# SchemeP1.net
KiCad netlist of a schematic drawn in Altium Designer
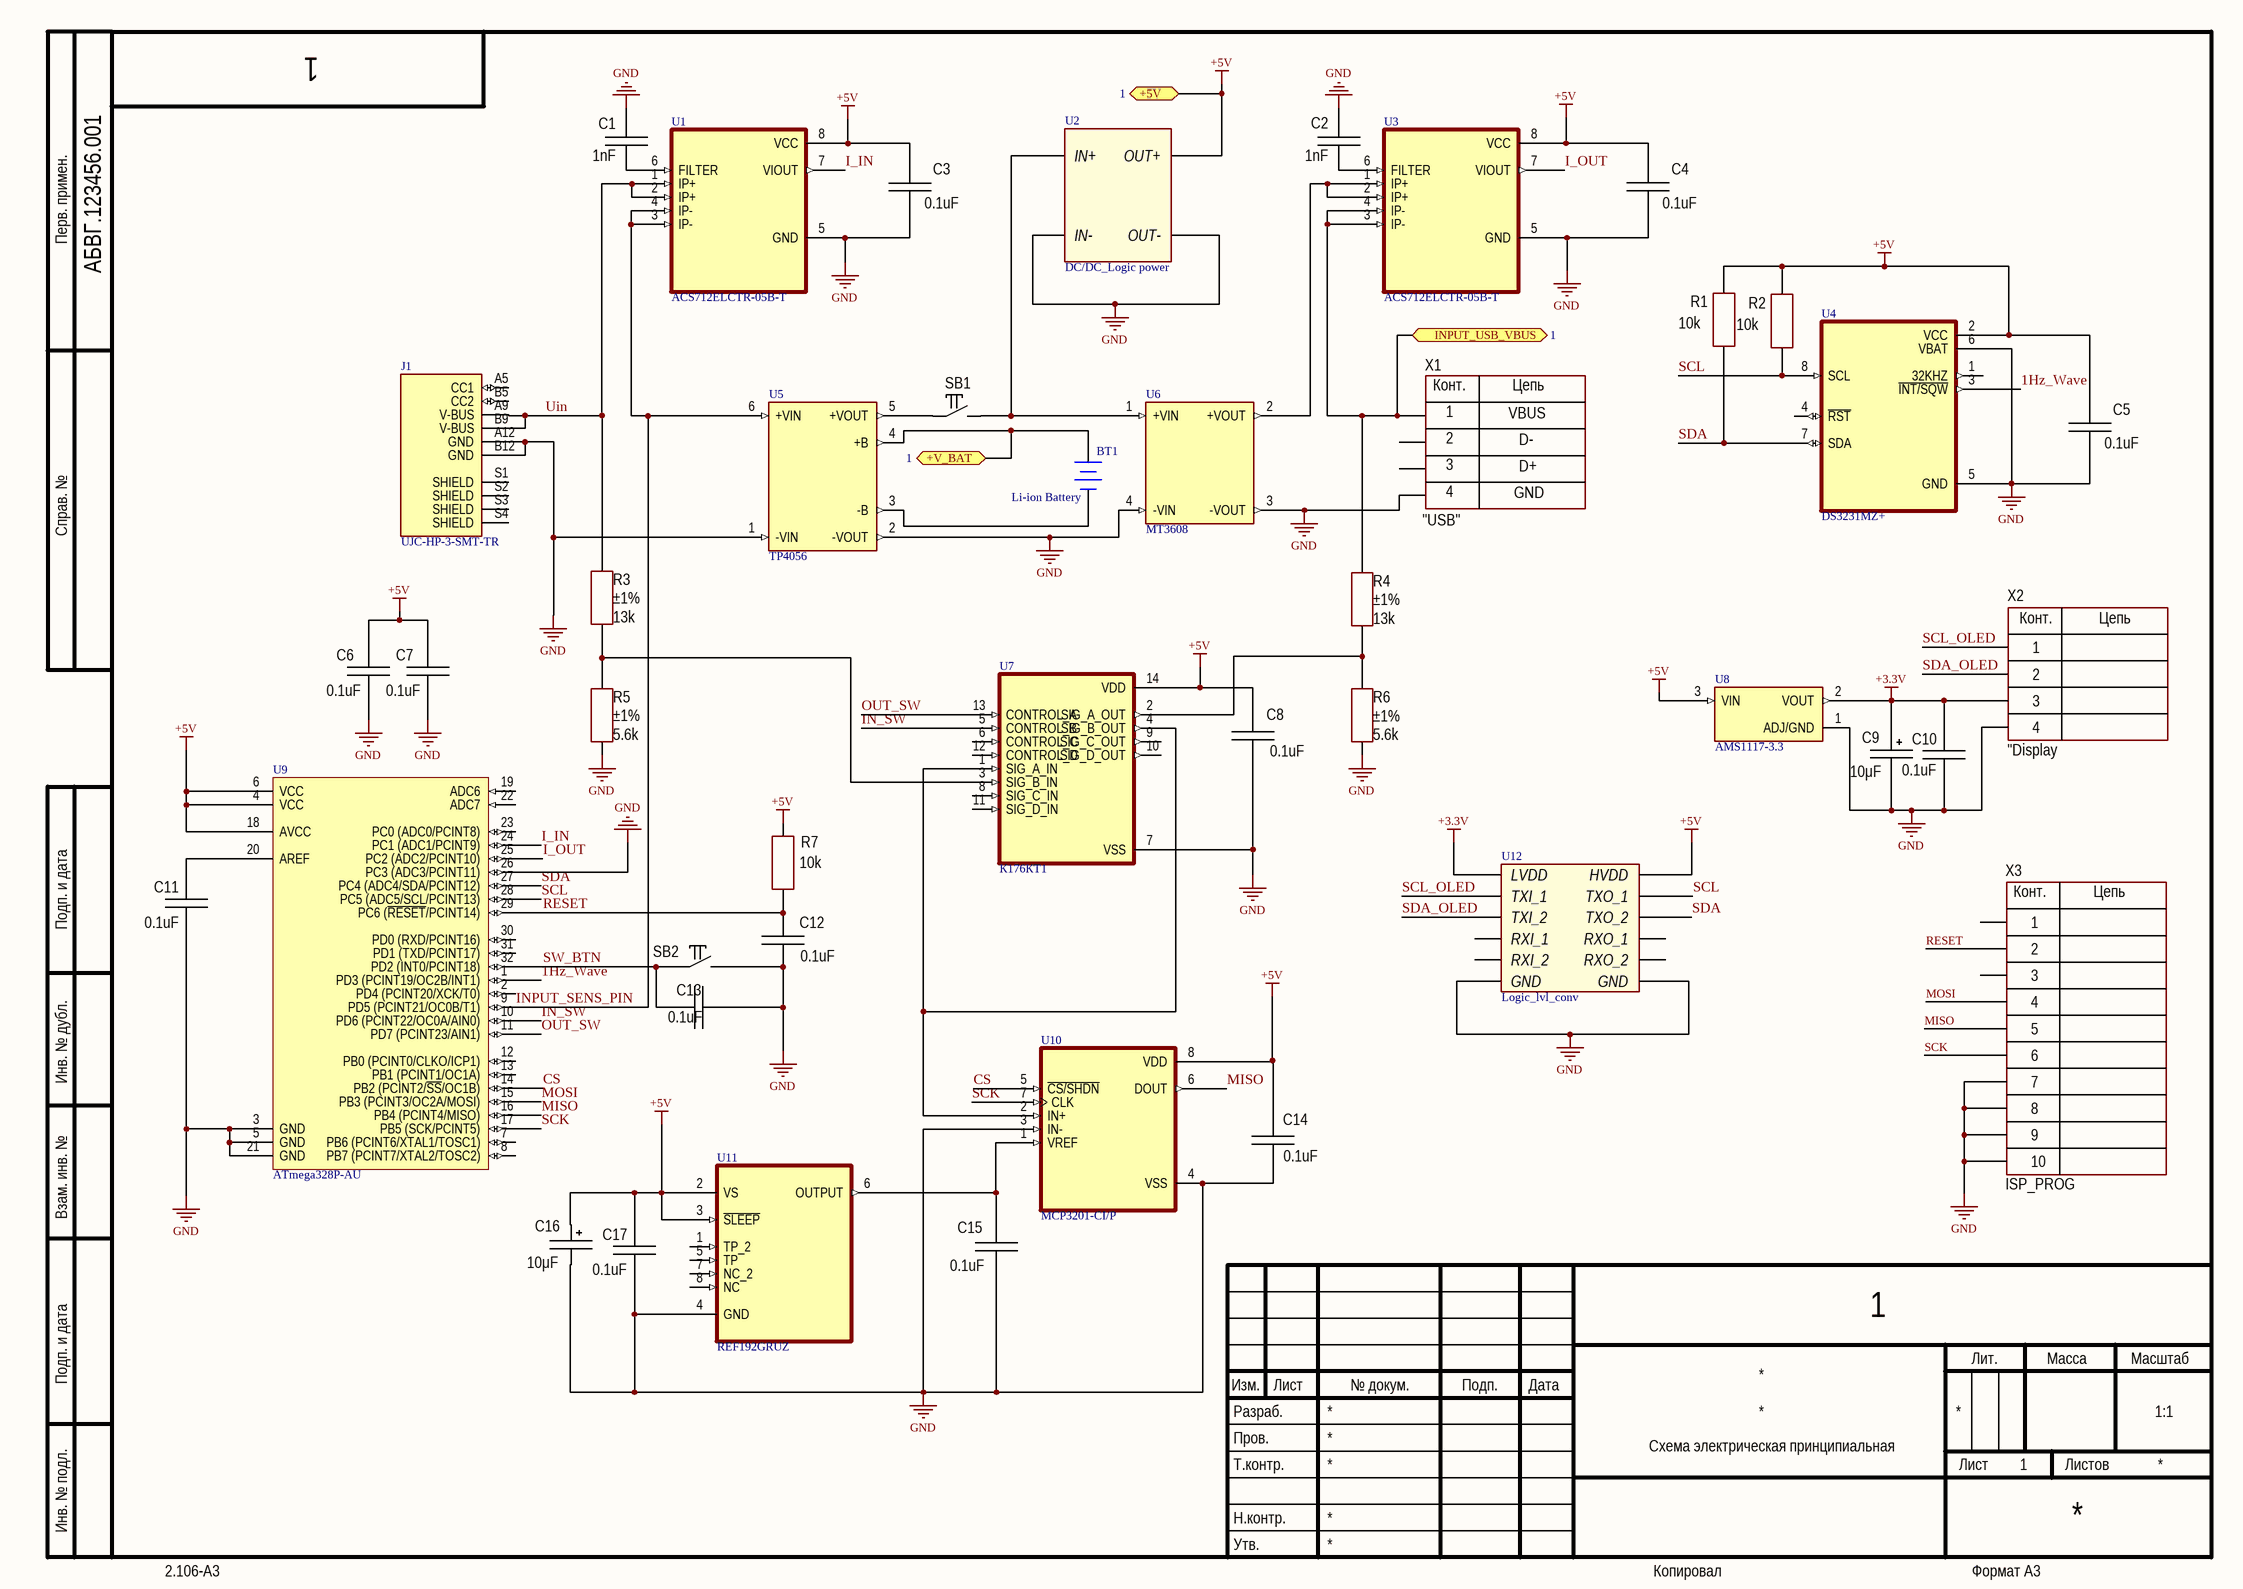
[diagram p0: SchemeP1.SchDoc]

(export (version "E")
  (design (tool "Eeschema 10.0.6"))
  (components
    (comp (ref "BT1")
      (value "Li-ion Battery")
      (footprint "BAT-2")
      (description "Multicell Battery")
      (fields (field (name "PUBLISHER") "Altium Limited"))
      (libsource (lib "Miscellaneous Devices") (part "Battery"))
    )
    (comp (ref "C1")
      (value "1nF")
      (footprint "standard:CH1206C")
      (libsource (lib "Discrete") (part "Capacitor"))
    )
    (comp (ref "C2")
      (value "1nF")
      (footprint "standard:CH1206C")
      (libsource (lib "Discrete") (part "Capacitor"))
    )
    (comp (ref "C3")
      (value "0.1uF")
      (footprint "standard:CH1206C")
      (libsource (lib "Discrete") (part "Capacitor"))
    )
    (comp (ref "C4")
      (value "0.1uF")
      (footprint "standard:CH1206C")
      (libsource (lib "Discrete") (part "Capacitor"))
    )
    (comp (ref "C5")
      (value "0.1uF")
      (footprint "standard:CH1206C")
      (libsource (lib "Discrete") (part "Capacitor"))
    )
    (comp (ref "C6")
      (value "0.1uF")
      (footprint "standard:CH1206C")
      (libsource (lib "Discrete") (part "Capacitor"))
    )
    (comp (ref "C7")
      (value "0.1uF")
      (footprint "standard:CH1206C")
      (libsource (lib "Discrete") (part "Capacitor"))
    )
    (comp (ref "C8")
      (value "0.1uF")
      (footprint "standard:CH1206C")
      (libsource (lib "Discrete") (part "Capacitor"))
    )
    (comp (ref "C9")
      (value "10μF")
      (footprint "StandardCase:CAP: TANTAL-A")
      (fields
        (field (name "MANUFACTURER") "AVX")
        (field (name "PARTNUMBER") "F930J107KAAAJ6")
        (field (name "VALUEMANUFACTURERPARTNUMBER") "Tantalum capacitor, 10μF, 6.3V, ±10%, 2Ohm, case A (3216), -55...+125°C")
      )
      (libsource (lib "Capacitor") (part "Tantal_A"))
    )
    (comp (ref "C10")
      (value "0.1uF")
      (footprint "standard:CH1206C")
      (libsource (lib "Discrete") (part "Capacitor"))
    )
    (comp (ref "C11")
      (value "0.1uF")
      (footprint "standard:CH1206C")
      (libsource (lib "Discrete") (part "Capacitor"))
    )
    (comp (ref "C12")
      (value "0.1uF")
      (footprint "standard:CH1206C")
      (libsource (lib "Discrete") (part "Capacitor"))
    )
    (comp (ref "C13")
      (value "0.1uF")
      (footprint "standard:CH1206C")
      (libsource (lib "Discrete") (part "Capacitor"))
    )
    (comp (ref "C14")
      (value "0.1uF")
      (footprint "standard:CH1206C")
      (libsource (lib "Discrete") (part "Capacitor"))
    )
    (comp (ref "C15")
      (value "0.1uF")
      (footprint "standard:CH1206C")
      (libsource (lib "Discrete") (part "Capacitor"))
    )
    (comp (ref "C16")
      (value "10μF")
      (footprint "StandardCase:CAP: TANTAL-A")
      (fields
        (field (name "MANUFACTURER") "AVX")
        (field (name "PARTNUMBER") "F930J107KAAAJ6")
        (field (name "VALUEMANUFACTURERPARTNUMBER") "Tantalum capacitor, 10μF, 6.3V, ±10%, 2Ohm, case A (3216), -55...+125°C")
      )
      (libsource (lib "Capacitor") (part "Tantal_A"))
    )
    (comp (ref "C17")
      (value "0.1uF")
      (footprint "standard:CH1206C")
      (libsource (lib "Discrete") (part "Capacitor"))
    )
    (comp (ref "J1")
      (value "UJC-HP-3-SMT-TR")
      (footprint "CUI_UJC-HP-3-SMT-TR")
      (description "Type C, 3 A, Right Angle, Surface Mount _SMT_, Power Only USB Receptacle")
      (fields (field (name "MF") "CUI Devices"))
      (libsource (lib "UJC-HP-3-SMT-TR") (part "UJC-HP-3-SMT-TR"))
    )
    (comp (ref "R1")
      (value "10k")
      (footprint "StandardCase:RES: 1206")
      (fields
        (field (name "MANUFACTURER") "Yageo")
        (field (name "PARTNUMBER") "RC1206JR-07100RL")
        (field (name "VALUEMANUFACTURERPARTNUMBER") "Resistor film, 10k, ±5%, 1206, 0.25W, -55...+125°C")
      )
      (libsource (lib "Resistor") (part "Resistor_1206"))
    )
    (comp (ref "R2")
      (value "10k")
      (footprint "StandardCase:RES: 1206")
      (fields
        (field (name "MANUFACTURER") "Yageo")
        (field (name "PARTNUMBER") "RC1206JR-07100RL")
        (field (name "VALUEMANUFACTURERPARTNUMBER") "Resistor film, 10k, ±5%, 1206, 0.25W, -55...+125°C")
      )
      (libsource (lib "Resistor") (part "Resistor_1206"))
    )
    (comp (ref "R3")
      (value "13k")
      (footprint "StandardCase:RES: 1206")
      (fields
        (field (name "MANUFACTURER") "Yageo")
        (field (name "PARTNUMBER") "RC1206JR-07100RL")
        (field (name "VALUEMANUFACTURERPARTNUMBER") "Resistor film, 13k, ±1%, 1206, 0.25W, -55...+125°C")
        (field (name "TOLERANCE") "±1%")
      )
      (libsource (lib "") (part "Resistor_1206_1"))
    )
    (comp (ref "R4")
      (value "13k")
      (footprint "StandardCase:RES: 1206")
      (fields
        (field (name "MANUFACTURER") "Yageo")
        (field (name "PARTNUMBER") "RC1206JR-07100RL")
        (field (name "VALUEMANUFACTURERPARTNUMBER") "Resistor film, 13k, ±1%, 1206, 0.25W, -55...+125°C")
        (field (name "TOLERANCE") "±1%")
      )
      (libsource (lib "") (part "Resistor_1206_1"))
    )
    (comp (ref "R5")
      (value "5.6k")
      (footprint "StandardCase:RES: 1206")
      (fields
        (field (name "MANUFACTURER") "Yageo")
        (field (name "PARTNUMBER") "RC1206JR-07100RL")
        (field (name "VALUEMANUFACTURERPARTNUMBER") "Resistor film, 5.6k, ±1%, 1206, 0.25W, -55...+125°C")
        (field (name "TOLERANCE") "±1%")
      )
      (libsource (lib "") (part "Resistor_1206_1"))
    )
    (comp (ref "R6")
      (value "5.6k")
      (footprint "StandardCase:RES: 1206")
      (fields
        (field (name "MANUFACTURER") "Yageo")
        (field (name "PARTNUMBER") "RC1206JR-07100RL")
        (field (name "VALUEMANUFACTURERPARTNUMBER") "Resistor film, 5.6k, ±1%, 1206, 0.25W, -55...+125°C")
        (field (name "TOLERANCE") "±1%")
      )
      (libsource (lib "") (part "Resistor_1206_1"))
    )
    (comp (ref "R7")
      (value "10k")
      (footprint "StandardCase:RES: 1206")
      (fields
        (field (name "MANUFACTURER") "Yageo")
        (field (name "PARTNUMBER") "RC1206JR-07100RL")
        (field (name "VALUEMANUFACTURERPARTNUMBER") "Resistor film, 10k, ±5%, 1206, 0.25W, -55...+125°C")
      )
      (libsource (lib "Resistor") (part "Resistor_1206"))
    )
    (comp (ref "SB1")
      (value "~")
      (footprint "CustomCase:BUT: 6x6")
      (fields
        (field (name "MANUFACTURER") "TE Connectivity")
        (field (name "VALUEMANUFACTURERPARTNUMBER") "Tactile button, 6x6mm")
        (field (name "PARTNUMBER") "FSM2JSMAATR")
      )
      (libsource (lib "Electromechanics") (part "Button_tactile"))
    )
    (comp (ref "SB2")
      (value "~")
      (footprint "CustomCase:BUT: 6x6")
      (fields
        (field (name "MANUFACTURER") "TE Connectivity")
        (field (name "VALUEMANUFACTURERPARTNUMBER") "Tactile button, 6x6mm")
        (field (name "PARTNUMBER") "FSM2JSMAATR")
      )
      (libsource (lib "Electromechanics") (part "Button_tactile"))
    )
    (comp (ref "U1")
      (value "ACS712ELCTR-05B-T")
      (footprint "SOIC127P600X175-8N")
      (description "Current Sensor 5A 1 Channel Hall Effect, Open Loop Bidirectional 8-SOIC _0.154, 3.90mm Width_")
      (fields
        (field (name "DIGI-KEY_PART_NUMBER") "620-1189-1-ND")
        (field (name "MF") "Allegro MicroSystems LLC")
      )
      (libsource (lib "ACS712ELCTR-05B-T") (part "ACS712ELCTR-05B-T"))
    )
    (comp (ref "U2") (value "DC/DC_Logic power") (footprint "DC_DC") (libsource (lib "DC_DC") (part "DC_DC")))
    (comp (ref "U3")
      (value "ACS712ELCTR-05B-T")
      (footprint "SOIC127P600X175-8N")
      (description "Current Sensor 5A 1 Channel Hall Effect, Open Loop Bidirectional 8-SOIC _0.154, 3.90mm Width_")
      (fields
        (field (name "DIGI-KEY_PART_NUMBER") "620-1189-1-ND")
        (field (name "MF") "Allegro MicroSystems LLC")
      )
      (libsource (lib "ACS712ELCTR-05B-T") (part "ACS712ELCTR-05B-T"))
    )
    (comp (ref "U4")
      (value "DS3231MZ+")
      (footprint "SOIC127P600X175-8N")
      (description "Real Time Clock _RTC_ IC Clock/Calendar IÂ²C, 2-Wire Serial 8-SOIC _0.154, 3.90mm Width_")
      (fields (field (name "MP") "DS3231MZ") (field (name "MF") "Maxim Integrated"))
      (libsource (lib "DS3231MZ_") (part "DS3231MZ+"))
    )
    (comp (ref "U5")
      (value "TP4056")
      (footprint "CONV_R0.25S-0505_E:CONV_R0.25S-0505/E")
      (description "Charge module Li-ion")
      (libsource (lib "R0.25S-0505_E") (part "TP4056"))
    )
    (comp (ref "U6")
      (value "MT3608")
      (footprint "CONV_RAZ-2405S:CONV_RAZ-2405S")
      (description "Step up DC/DC")
      (libsource (lib "RAZ-2405S") (part "MT3608"))
    )
    (comp (ref "U7")
      (value "К176КТ1")
      (footprint "DIP794W45P254L1969H508Q14")
      (description "100-pA, 20-V, 1:1 (SPST), 4-channel analog switch 14-PDIP -55 to 125")
      (fields (field (name "MP") "CD4016BE") (field (name "MF") "Texas Instruments"))
      (libsource (lib "CD4016BE") (part "CD4016BE"))
    )
    (comp (ref "U8")
      (value "AMS1117-3.3")
      (footprint "SOT229P700X180-4N")
      (description "Sot223/Pkg 1-Amp 3.3-Volt Low Drop Out Voltage Regulatator")
      (fields (field (name "MF") "Advanced Monolithic Systems"))
      (libsource (lib "AMS1117-3.3") (part "AMS1117-3.3"))
    )
    (comp (ref "U9")
      (value "ATmega328P-AU")
      (footprint "32A_M")
      (fields (field (name "PUBLISHER") "Altium Limited"))
      (libsource (lib "Atmel Microcontroller 8-Bit megaAVR") (part "ATmega328P-AU"))
    )
    (comp (ref "U10")
      (value "MCP3201-CI/P")
      (footprint "DIP787W46P254L927H533Q8")
      (description "12 Bit Analog to Digital Converter 1 Input 1 SAR 8-PDIP")
      (fields (field (name "MF") "Microchip"))
      (libsource (lib "MCP3201-CI_P") (part "MCP3201-CI/P"))
    )
    (comp (ref "U11")
      (value "REF192GRUZ")
      (footprint "SOIC_N-8 - duplicate1")
      (description "Series Voltage Reference IC Â±0.4% 8-TSSOP")
      (fields (field (name "MF") "Analog Devices"))
      (libsource (lib "REF192GRUZ") (part "REF192GRUZ"))
    )
    (comp (ref "U12") (value "Logic_lvl_conv") (libsource (lib "Logic_lvl_conv") (part "Logic_lvl_conv")))
    (comp (ref "X1")
      (value "\"USB\"")
      (footprint "custom:CON: USB-A")
      (description "USB")
      (fields (field (name "MANUFACTURER") "TE Connectivity"))
      (libsource (lib "Connectors") (part "USB-A"))
    )
    (comp (ref "X2")
      (value "~")
      (footprint "CustomCase:CON: PLS-4")
      (fields
        (field (name "MANUFACTURER") "Connfly")
        (field (name "VALUEMANUFACTURERPARTNUMBER") "Connector, 4pin, 2.54mm, 500VAC, 3A")
        (field (name "PARTNUMBER") "PLS-4")
        (field (name "COMMENTTEXT") "\"Display")
      )
      (libsource (lib "Connector") (part "PLS-4"))
    )
    (comp (ref "X3")
      (value "ISP_PROG")
      (footprint "custom:CON: IDC-10MS")
      (libsource (lib "Connectors") (part "10-Connector"))
    )
  )
  (nets
    (net (code "1") (name "+3.3V") (class "Default")
      (node (ref "C10") (pin "1") (pinfunction "1_1") (pintype "power_in"))
      (node (ref "C9") (pin "1") (pinfunction "1_1") (pintype "power_in"))
      (node (ref "U12") (pin "9") (pinfunction "LVDD_9") (pintype "passive"))
      (node (ref "U8") (pin "2") (pinfunction "VOUT_2") (pintype "output"))
      (node (ref "X2") (pin "3") (pinfunction "3_3") (pintype "power_in"))
    )
    (net (code "2") (name "+5V") (class "Default")
      (node (ref "C14") (pin "1") (pinfunction "1_1") (pintype "power_in"))
      (node (ref "C16") (pin "1") (pinfunction "1_1") (pintype "power_in"))
      (node (ref "C17") (pin "1") (pinfunction "1_1") (pintype "power_in"))
      (node (ref "C3") (pin "1") (pinfunction "1_1") (pintype "power_in"))
      (node (ref "C4") (pin "1") (pinfunction "1_1") (pintype "power_in"))
      (node (ref "C5") (pin "1") (pinfunction "1_1") (pintype "power_in"))
      (node (ref "C6") (pin "1") (pinfunction "1_1") (pintype "power_in"))
      (node (ref "C7") (pin "1") (pinfunction "1_1") (pintype "power_in"))
      (node (ref "C8") (pin "1") (pinfunction "1_1") (pintype "power_in"))
      (node (ref "R1") (pin "1") (pinfunction "1_1") (pintype "passive"))
      (node (ref "R2") (pin "1") (pinfunction "1_1") (pintype "passive"))
      (node (ref "R7") (pin "1") (pinfunction "1_1") (pintype "passive"))
      (node (ref "U1") (pin "8") (pinfunction "VCC_8") (pintype "power_in"))
      (node (ref "U10") (pin "8") (pinfunction "VDD_8") (pintype "power_in"))
      (node (ref "U11") (pin "2") (pinfunction "VS_2") (pintype "power_in"))
      (node (ref "U11") (pin "3") (pinfunction "~{SLEEP}_3") (pintype "input"))
      (node (ref "U12") (pin "4") (pinfunction "HVDD_4") (pintype "passive"))
      (node (ref "U2") (pin "4") (pinfunction "OUT+_4") (pintype "passive"))
      (node (ref "U3") (pin "8") (pinfunction "VCC_8") (pintype "power_in"))
      (node (ref "U4") (pin "2") (pinfunction "VCC_2") (pintype "power_in"))
      (node (ref "U7") (pin "14") (pinfunction "VDD_14") (pintype "power_in"))
      (node (ref "U8") (pin "3") (pinfunction "VIN_3") (pintype "input"))
      (node (ref "U9") (pin "18") (pinfunction "AVCC_18") (pintype "power_in"))
      (node (ref "U9") (pin "4") (pinfunction "VCC_4") (pintype "power_in"))
      (node (ref "U9") (pin "6") (pinfunction "VCC_6") (pintype "power_in"))
    )
    (net (code "3") (name "/+V_BAT") (class "Default")
      (node (ref "BT1") (pin "1") (pinfunction "+_1") (pintype "passive"))
      (node (ref "U5") (pin "4") (pinfunction "+B_4") (pintype "output"))
    )
    (net (code "4") (name "/1Hz_Wave") (class "Default")
      (node (ref "U4") (pin "3") (pinfunction "~{INT/SQW}_3") (pintype "output"))
      (node (ref "U9") (pin "1") (pinfunction "PD3_(PCINT19/OC2B/INT1)_1") (pintype "bidirectional"))
    )
    (net (code "5") (name "/CS") (class "Default")
      (node (ref "U10") (pin "5") (pinfunction "~{CS/SHDN}_5") (pintype "input"))
      (node (ref "U9") (pin "14") (pinfunction "PB2_(PCINT2/~{SS}/OC1B)_14") (pintype "bidirectional"))
    )
    (net (code "6") (name "/INPUT_SENS_PIN") (class "Default")
      (node (ref "U1") (pin "3") (pinfunction "IP-_3") (pintype "input"))
      (node (ref "U1") (pin "4") (pinfunction "IP-_4") (pintype "input"))
      (node (ref "U5") (pin "6") (pinfunction "+VIN_6") (pintype "input"))
      (node (ref "U9") (pin "9") (pinfunction "PD5_(PCINT21/OC0B/T1)_9") (pintype "bidirectional"))
    )
    (net (code "7") (name "/INPUT_USB_VBUS") (class "Default")
      (node (ref "R4") (pin "2") (pinfunction "2_2") (pintype "passive"))
      (node (ref "U3") (pin "3") (pinfunction "IP-_3") (pintype "input"))
      (node (ref "U3") (pin "4") (pinfunction "IP-_4") (pintype "input"))
      (node (ref "X1") (pin "1") (pintype "passive"))
    )
    (net (code "8") (name "/IN_SW") (class "Default")
      (node (ref "U7") (pin "5") (pinfunction "CONTROL_B_5") (pintype "input"))
      (node (ref "U9") (pin "10") (pinfunction "PD6_(PCINT22/OC0A/AIN0)_10") (pintype "bidirectional"))
    )
    (net (code "9") (name "/I_IN") (class "Default")
      (node (ref "U1") (pin "7") (pinfunction "VIOUT_7") (pintype "output"))
      (node (ref "U9") (pin "24") (pinfunction "PC1_(ADC1/PCINT9)_24") (pintype "bidirectional"))
    )
    (net (code "10") (name "/I_OUT") (class "Default")
      (node (ref "U3") (pin "7") (pinfunction "VIOUT_7") (pintype "output"))
      (node (ref "U9") (pin "25") (pinfunction "PC2_(ADC2/PCINT10)_25") (pintype "bidirectional"))
    )
    (net (code "11") (name "/MISO") (class "Default")
      (node (ref "U10") (pin "6") (pinfunction "DOUT_6") (pintype "output"))
      (node (ref "U9") (pin "16") (pinfunction "PB4_(PCINT4/MISO)_16") (pintype "bidirectional"))
      (node (ref "X3") (pin "5") (pinfunction "5_5") (pintype "power_in"))
    )
    (net (code "12") (name "/MOSI") (class "Default")
      (node (ref "U9") (pin "15") (pinfunction "PB3_(PCINT3/OC2A/MOSI)_15") (pintype "bidirectional"))
      (node (ref "X3") (pin "4") (pinfunction "4_4") (pintype "power_in"))
    )
    (net (code "13") (name "/OUT_SW") (class "Default")
      (node (ref "U7") (pin "13") (pinfunction "CONTROL_A_13") (pintype "input"))
      (node (ref "U9") (pin "11") (pinfunction "PD7_(PCINT23/AIN1)_11") (pintype "bidirectional"))
    )
    (net (code "14") (name "/RESET") (class "Default")
      (node (ref "C12") (pin "1") (pinfunction "1_1") (pintype "power_in"))
      (node (ref "R7") (pin "2") (pinfunction "2_2") (pintype "passive"))
      (node (ref "U9") (pin "29") (pinfunction "PC6_(~{RESET}/PCINT14)_29") (pintype "bidirectional"))
      (node (ref "X3") (pin "2") (pinfunction "2_2") (pintype "passive"))
    )
    (net (code "15") (name "/SCK") (class "Default")
      (node (ref "U10") (pin "7") (pinfunction "CLK_7") (pintype "input"))
      (node (ref "U9") (pin "17") (pinfunction "PB5_(SCK/PCINT5)_17") (pintype "bidirectional"))
      (node (ref "X3") (pin "6") (pinfunction "6_6") (pintype "power_in"))
    )
    (net (code "16") (name "/SCL") (class "Default")
      (node (ref "R2") (pin "2") (pinfunction "2_2") (pintype "passive"))
      (node (ref "U12") (pin "6") (pinfunction "TXO_1_6") (pintype "passive"))
      (node (ref "U4") (pin "8") (pinfunction "SCL_8") (pintype "input"))
      (node (ref "U9") (pin "28") (pinfunction "PC5_(ADC5/SCL/PCINT13)_28") (pintype "bidirectional"))
    )
    (net (code "17") (name "/SCL_OLED") (class "Default")
      (node (ref "U12") (pin "7") (pinfunction "TXI_1_7") (pintype "passive"))
      (node (ref "X2") (pin "1") (pinfunction "1_1") (pintype "passive"))
    )
    (net (code "18") (name "/SDA") (class "Default")
      (node (ref "R1") (pin "2") (pinfunction "2_2") (pintype "passive"))
      (node (ref "U12") (pin "1") (pinfunction "TXO_2_1") (pintype "passive"))
      (node (ref "U4") (pin "7") (pinfunction "SDA_7") (pintype "bidirectional"))
      (node (ref "U9") (pin "27") (pinfunction "PC4_(ADC4/SDA/PCINT12)_27") (pintype "bidirectional"))
    )
    (net (code "19") (name "/SDA_OLED") (class "Default")
      (node (ref "U12") (pin "12") (pinfunction "TXI_2_12") (pintype "passive"))
      (node (ref "X2") (pin "2") (pinfunction "2_2") (pintype "passive"))
    )
    (net (code "20") (name "/SW_BTN") (class "Default")
      (node (ref "C13") (pin "1") (pinfunction "1_1") (pintype "power_in"))
      (node (ref "SB2") (pin "1") (pinfunction "1_1") (pintype "passive"))
      (node (ref "U9") (pin "32") (pinfunction "PD2_(INT0/PCINT18)_32") (pintype "bidirectional"))
    )
    (net (code "21") (name "/Uin") (class "Default")
      (node (ref "J1") (pin "A9") (pinfunction "V-BUS_A9") (pintype "power_in"))
      (node (ref "J1") (pin "B9") (pinfunction "V-BUS_B9") (pintype "power_in"))
      (node (ref "R3") (pin "2") (pinfunction "2_2") (pintype "passive"))
      (node (ref "U1") (pin "1") (pinfunction "IP+_1") (pintype "input"))
      (node (ref "U1") (pin "2") (pinfunction "IP+_2") (pintype "input"))
    )
    (net (code "22") (name "GND") (class "Default")
      (node (ref "C1") (pin "1") (pinfunction "1_1") (pintype "power_in"))
      (node (ref "C10") (pin "2") (pinfunction "2_2") (pintype "power_in"))
      (node (ref "C11") (pin "2") (pinfunction "2_2") (pintype "power_in"))
      (node (ref "C12") (pin "2") (pinfunction "2_2") (pintype "power_in"))
      (node (ref "C13") (pin "2") (pinfunction "2_2") (pintype "power_in"))
      (node (ref "C14") (pin "2") (pinfunction "2_2") (pintype "power_in"))
      (node (ref "C15") (pin "2") (pinfunction "2_2") (pintype "power_in"))
      (node (ref "C16") (pin "2") (pinfunction "2_2") (pintype "power_in"))
      (node (ref "C17") (pin "2") (pinfunction "2_2") (pintype "power_in"))
      (node (ref "C2") (pin "1") (pinfunction "1_1") (pintype "power_in"))
      (node (ref "C3") (pin "2") (pinfunction "2_2") (pintype "power_in"))
      (node (ref "C4") (pin "2") (pinfunction "2_2") (pintype "power_in"))
      (node (ref "C5") (pin "2") (pinfunction "2_2") (pintype "power_in"))
      (node (ref "C6") (pin "2") (pinfunction "2_2") (pintype "power_in"))
      (node (ref "C7") (pin "2") (pinfunction "2_2") (pintype "power_in"))
      (node (ref "C8") (pin "2") (pinfunction "2_2") (pintype "power_in"))
      (node (ref "C9") (pin "2") (pinfunction "2_2") (pintype "power_in"))
      (node (ref "J1") (pin "A12") (pinfunction "GND_A12") (pintype "power_in"))
      (node (ref "J1") (pin "B12") (pinfunction "GND_B12") (pintype "power_in"))
      (node (ref "R5") (pin "1") (pinfunction "1_1") (pintype "passive"))
      (node (ref "R6") (pin "1") (pinfunction "1_1") (pintype "passive"))
      (node (ref "SB2") (pin "2") (pinfunction "2_2") (pintype "passive"))
      (node (ref "U1") (pin "5") (pinfunction "GND_5") (pintype "power_in"))
      (node (ref "U10") (pin "3") (pinfunction "IN-_3") (pintype "input"))
      (node (ref "U10") (pin "4") (pinfunction "VSS_4") (pintype "power_in"))
      (node (ref "U11") (pin "4") (pinfunction "GND_4") (pintype "passive"))
      (node (ref "U12") (pin "10") (pinfunction "GND_10") (pintype "passive"))
      (node (ref "U12") (pin "3") (pinfunction "GND_3") (pintype "passive"))
      (node (ref "U2") (pin "1") (pinfunction "IN-_1") (pintype "passive"))
      (node (ref "U2") (pin "3") (pinfunction "OUT-_3") (pintype "passive"))
      (node (ref "U3") (pin "5") (pinfunction "GND_5") (pintype "power_in"))
      (node (ref "U4") (pin "5") (pinfunction "GND_5") (pintype "power_in"))
      (node (ref "U4") (pin "6") (pinfunction "VBAT_6") (pintype "power_in"))
      (node (ref "U5") (pin "1") (pinfunction "-VIN_1") (pintype "input"))
      (node (ref "U5") (pin "2") (pinfunction "-VOUT_2") (pintype "output"))
      (node (ref "U6") (pin "3") (pinfunction "-VOUT_3") (pintype "output"))
      (node (ref "U6") (pin "4") (pinfunction "-VIN_4") (pintype "input"))
      (node (ref "U7") (pin "7") (pinfunction "VSS_7") (pintype "power_in"))
      (node (ref "U8") (pin "1") (pinfunction "ADJ/GND_1") (pintype "power_in"))
      (node (ref "U9") (pin "21") (pinfunction "GND_21") (pintype "power_in"))
      (node (ref "U9") (pin "26") (pinfunction "PC3_(ADC3/PCINT11)_26") (pintype "bidirectional"))
      (node (ref "U9") (pin "3") (pinfunction "GND_3") (pintype "power_in"))
      (node (ref "U9") (pin "5") (pinfunction "GND_5") (pintype "power_in"))
      (node (ref "X1") (pin "4") (pinfunction "4_4") (pintype "passive"))
      (node (ref "X2") (pin "4") (pinfunction "4_4") (pintype "power_in"))
      (node (ref "X3") (pin "10") (pinfunction "10_10") (pintype "power_in"))
      (node (ref "X3") (pin "7") (pinfunction "7_7") (pintype "power_in"))
      (node (ref "X3") (pin "8") (pinfunction "8_8") (pintype "power_in"))
      (node (ref "X3") (pin "9") (pinfunction "9_9") (pintype "power_in"))
    )
    (net (code "23") (name "Net-(BT1--)") (class "Default")
      (node (ref "BT1") (pin "2") (pinfunction "-_2") (pintype "passive"))
      (node (ref "U5") (pin "3") (pinfunction "-B_3") (pintype "output"))
    )
    (net (code "24") (name "Net-(U1-FILTER)") (class "Default")
      (node (ref "C1") (pin "2") (pinfunction "2_2") (pintype "power_in"))
      (node (ref "U1") (pin "6") (pinfunction "FILTER_6") (pintype "input"))
    )
    (net (code "25") (name "Net-(U2-IN+)") (class "Default")
      (node (ref "SB1") (pin "2") (pinfunction "2_2") (pintype "passive"))
      (node (ref "U2") (pin "2") (pinfunction "IN+_2") (pintype "passive"))
      (node (ref "U6") (pin "1") (pinfunction "+VIN_1") (pintype "input"))
    )
    (net (code "26") (name "Net-(U3-FILTER)") (class "Default")
      (node (ref "C2") (pin "2") (pinfunction "2_2") (pintype "power_in"))
      (node (ref "U3") (pin "6") (pinfunction "FILTER_6") (pintype "input"))
    )
    (net (code "27") (name "Net-(U5-+VOUT)") (class "Default")
      (node (ref "SB1") (pin "1") (pinfunction "1_1") (pintype "passive"))
      (node (ref "U5") (pin "5") (pinfunction "+VOUT_5") (pintype "output"))
    )
    (net (code "28") (name "Net-(U6-+VOUT)") (class "Default")
      (node (ref "U3") (pin "1") (pinfunction "IP+_1") (pintype "input"))
      (node (ref "U3") (pin "2") (pinfunction "IP+_2") (pintype "input"))
      (node (ref "U6") (pin "2") (pinfunction "+VOUT_2") (pintype "output"))
    )
    (net (code "29") (name "Net-(U7-SIG_A_OUT)") (class "Default")
      (node (ref "R4") (pin "1") (pinfunction "1_1") (pintype "passive"))
      (node (ref "R6") (pin "2") (pinfunction "2_2") (pintype "passive"))
      (node (ref "U7") (pin "2") (pinfunction "SIG_A_OUT_2") (pintype "output"))
    )
    (net (code "30") (name "Net-(U7-SIG_B_IN)") (class "Default")
      (node (ref "R3") (pin "1") (pinfunction "1_1") (pintype "passive"))
      (node (ref "R5") (pin "2") (pinfunction "2_2") (pintype "passive"))
      (node (ref "U7") (pin "3") (pinfunction "SIG_B_IN_3") (pintype "input"))
    )
    (net (code "31") (name "Net-(U9-AREF)") (class "Default")
      (node (ref "C11") (pin "1") (pinfunction "1_1") (pintype "power_in"))
      (node (ref "U9") (pin "20") (pinfunction "AREF_20") (pintype "passive"))
    )
    (net (code "32") (name "Net-(U10-IN+)") (class "Default")
      (node (ref "U10") (pin "2") (pinfunction "IN+_2") (pintype "input"))
      (node (ref "U7") (pin "1") (pinfunction "SIG_A_IN_1") (pintype "input"))
      (node (ref "U7") (pin "4") (pinfunction "SIG_B_OUT_4") (pintype "output"))
    )
    (net (code "33") (name "Net-(U10-VREF)") (class "Default")
      (node (ref "C15") (pin "1") (pinfunction "1_1") (pintype "power_in"))
      (node (ref "U10") (pin "1") (pinfunction "VREF_1") (pintype "input"))
      (node (ref "U11") (pin "6") (pinfunction "OUTPUT_6") (pintype "output"))
    )
    (net (code "34") (name "unconnected-(J1-CC1-PadA5)") (class "Default")
      (node (ref "J1") (pin "A5") (pinfunction "CC1_A5") (pintype "bidirectional"))
    )
    (net (code "35") (name "unconnected-(J1-CC2-PadB5)") (class "Default")
      (node (ref "J1") (pin "B5") (pinfunction "CC2_B5") (pintype "bidirectional"))
    )
    (net (code "36") (name "unconnected-(J1-SHIELD-PadS1)") (class "Default")
      (node (ref "J1") (pin "S1") (pinfunction "SHIELD_S1") (pintype "passive"))
    )
    (net (code "37") (name "unconnected-(J1-SHIELD-PadS2)") (class "Default")
      (node (ref "J1") (pin "S2") (pinfunction "SHIELD_S2") (pintype "passive"))
    )
    (net (code "38") (name "unconnected-(J1-SHIELD-PadS3)") (class "Default")
      (node (ref "J1") (pin "S3") (pinfunction "SHIELD_S3") (pintype "passive"))
    )
    (net (code "39") (name "unconnected-(J1-SHIELD-PadS4)") (class "Default")
      (node (ref "J1") (pin "S4") (pinfunction "SHIELD_S4") (pintype "passive"))
    )
    (net (code "40") (name "unconnected-(U4-32KHZ-Pad1)") (class "Default")
      (node (ref "U4") (pin "1") (pinfunction "32KHZ_1") (pintype "output"))
    )
    (net (code "41") (name "unconnected-(U4-~{RST}-Pad4)") (class "Default")
      (node (ref "U4") (pin "4") (pinfunction "~{RST}_4") (pintype "bidirectional"))
    )
    (net (code "42") (name "unconnected-(U7-CONTROL_C-Pad6)") (class "Default")
      (node (ref "U7") (pin "6") (pinfunction "CONTROL_C_6") (pintype "input"))
    )
    (net (code "43") (name "unconnected-(U7-CONTROL_D-Pad12)") (class "Default")
      (node (ref "U7") (pin "12") (pinfunction "CONTROL_D_12") (pintype "input"))
    )
    (net (code "44") (name "unconnected-(U7-SIG_C_IN-Pad8)") (class "Default")
      (node (ref "U7") (pin "8") (pinfunction "SIG_C_IN_8") (pintype "input"))
    )
    (net (code "45") (name "unconnected-(U7-SIG_C_OUT-Pad9)") (class "Default")
      (node (ref "U7") (pin "9") (pinfunction "SIG_C_OUT_9") (pintype "output"))
    )
    (net (code "46") (name "unconnected-(U7-SIG_D_IN-Pad11)") (class "Default")
      (node (ref "U7") (pin "11") (pinfunction "SIG_D_IN_11") (pintype "input"))
    )
    (net (code "47") (name "unconnected-(U7-SIG_D_OUT-Pad10)") (class "Default")
      (node (ref "U7") (pin "10") (pinfunction "SIG_D_OUT_10") (pintype "output"))
    )
    (net (code "48") (name "unconnected-(U9-ADC6-Pad19)") (class "Default")
      (node (ref "U9") (pin "19") (pinfunction "ADC6_19") (pintype "input"))
    )
    (net (code "49") (name "unconnected-(U9-ADC7-Pad22)") (class "Default")
      (node (ref "U9") (pin "22") (pinfunction "ADC7_22") (pintype "input"))
    )
    (net (code "50") (name "unconnected-(U9-PB0_(PCINT0{slash}CLKO{slash}ICP1)-Pad12)") (class "Default")
      (node (ref "U9") (pin "12") (pinfunction "PB0_(PCINT0/CLKO/ICP1)_12") (pintype "bidirectional"))
    )
    (net (code "51") (name "unconnected-(U9-PB1_(PCINT1{slash}OC1A)-Pad13)") (class "Default")
      (node (ref "U9") (pin "13") (pinfunction "PB1_(PCINT1/OC1A)_13") (pintype "bidirectional"))
    )
    (net (code "52") (name "unconnected-(U9-PB6_(PCINT6{slash}XTAL1{slash}TOSC1)-Pad7)") (class "Default")
      (node (ref "U9") (pin "7") (pinfunction "PB6_(PCINT6/XTAL1/TOSC1)_7") (pintype "bidirectional"))
    )
    (net (code "53") (name "unconnected-(U9-PB7_(PCINT7{slash}XTAL2{slash}TOSC2)-Pad8)") (class "Default")
      (node (ref "U9") (pin "8") (pinfunction "PB7_(PCINT7/XTAL2/TOSC2)_8") (pintype "bidirectional"))
    )
    (net (code "54") (name "unconnected-(U9-PC0_(ADC0{slash}PCINT8)-Pad23)") (class "Default")
      (node (ref "U9") (pin "23") (pinfunction "PC0_(ADC0/PCINT8)_23") (pintype "bidirectional"))
    )
    (net (code "55") (name "unconnected-(U9-PD0_(RXD{slash}PCINT16)-Pad30)") (class "Default")
      (node (ref "U9") (pin "30") (pinfunction "PD0_(RXD/PCINT16)_30") (pintype "bidirectional"))
    )
    (net (code "56") (name "unconnected-(U9-PD1_(TXD{slash}PCINT17)-Pad31)") (class "Default")
      (node (ref "U9") (pin "31") (pinfunction "PD1_(TXD/PCINT17)_31") (pintype "bidirectional"))
    )
    (net (code "57") (name "unconnected-(U9-PD4_(PCINT20{slash}XCK{slash}T0)-Pad2)") (class "Default")
      (node (ref "U9") (pin "2") (pinfunction "PD4_(PCINT20/XCK/T0)_2") (pintype "bidirectional"))
    )
    (net (code "58") (name "unconnected-(U11-NC-Pad8)") (class "Default")
      (node (ref "U11") (pin "8") (pinfunction "NC_8") (pintype "input"))
    )
    (net (code "59") (name "unconnected-(U11-NC_2-Pad7)") (class "Default")
      (node (ref "U11") (pin "7") (pinfunction "NC_2_7") (pintype "input"))
    )
    (net (code "60") (name "unconnected-(U11-TP-Pad5)") (class "Default")
      (node (ref "U11") (pin "5") (pinfunction "TP_5") (pintype "input"))
    )
    (net (code "61") (name "unconnected-(U11-TP_2-Pad1)") (class "Default")
      (node (ref "U11") (pin "1") (pinfunction "TP_2_1") (pintype "input"))
    )
    (net (code "62") (name "unconnected-(U12-RXI_1-Pad5)") (class "Default")
      (node (ref "U12") (pin "5") (pinfunction "RXI_1_5") (pintype "passive"))
    )
    (net (code "63") (name "unconnected-(U12-RXI_2-Pad2)") (class "Default")
      (node (ref "U12") (pin "2") (pinfunction "RXI_2_2") (pintype "passive"))
    )
    (net (code "64") (name "unconnected-(U12-RXO_1-Pad8)") (class "Default")
      (node (ref "U12") (pin "8") (pinfunction "RXO_1_8") (pintype "passive"))
    )
    (net (code "65") (name "unconnected-(U12-RXO_2-Pad11)") (class "Default")
      (node (ref "U12") (pin "11") (pinfunction "RXO_2_11") (pintype "passive"))
    )
    (net (code "66") (name "unconnected-(X1-Pad2)") (class "Default")
      (node (ref "X1") (pin "2") (pinfunction "2_2") (pintype "passive"))
    )
    (net (code "67") (name "unconnected-(X1-Pad3)") (class "Default")
      (node (ref "X1") (pin "3") (pinfunction "3_3") (pintype "passive"))
    )
    (net (code "68") (name "unconnected-(X3-Pad1)") (class "Default")
      (node (ref "X3") (pin "1") (pinfunction "1_1") (pintype "passive"))
    )
    (net (code "69") (name "unconnected-(X3-Pad3)") (class "Default")
      (node (ref "X3") (pin "3") (pinfunction "3_3") (pintype "power_in"))
    )
  )
)
